# v1.net
KiCad netlist of a schematic drawn in EAGLE
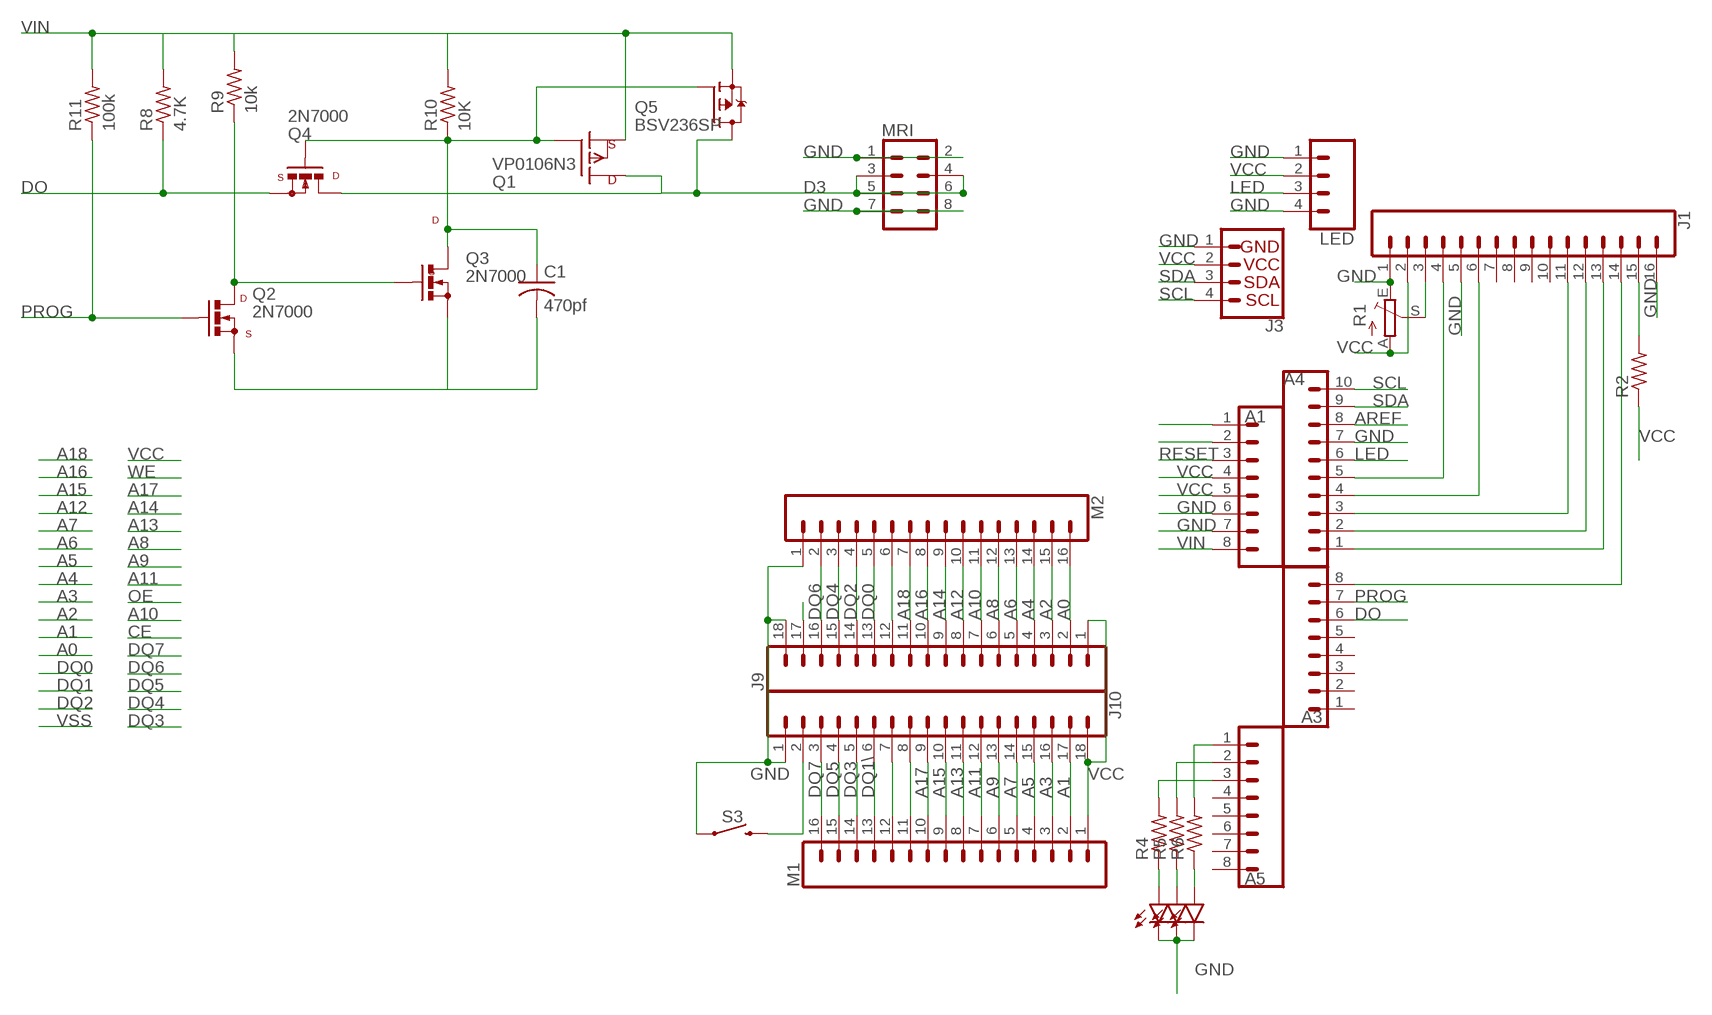
[diagram p0: schematic, sheet 1]

(export (version "E")
  (design (tool "Eeschema 10.0.6"))
  (components
    (comp (ref "A1")
      (value "CONN_08FEMALE_LOCK")
      (footprint "eagle-import:1X08_FEMALE_LOCK")
      (libsource (lib "eagle-import") (part "CONN_08FEMALE_LOCK"))
    )
    (comp (ref "A3")
      (value "CONN_08FEMALE_LOCK")
      (footprint "eagle-import:1X08_FEMALE_LOCK")
      (libsource (lib "eagle-import") (part "CONN_08FEMALE_LOCK"))
    )
    (comp (ref "A4")
      (value "CONN_10LOCK")
      (footprint "eagle-import:1X10_LOCK")
      (libsource (lib "eagle-import") (part "CONN_10LOCK"))
    )
    (comp (ref "A5")
      (value "CONN_08FEMALE_LOCK")
      (footprint "eagle-import:1X08_FEMALE_LOCK")
      (libsource (lib "eagle-import") (part "CONN_08FEMALE_LOCK"))
    )
    (comp (ref "C1")
      (value "470pf")
      (footprint "eagle-import:C025-025X050")
      (libsource (lib "eagle-import") (part "C-US025-025X050"))
    )
    (comp (ref "D1")
      (value "LED3MM")
      (footprint "eagle-import:LED_3MM")
      (libsource (lib "eagle-import") (part "LED3MM"))
    )
    (comp (ref "D2")
      (value "LED3MM")
      (footprint "eagle-import:LED_3MM")
      (libsource (lib "eagle-import") (part "LED3MM"))
    )
    (comp (ref "D3")
      (value "LED3MM")
      (footprint "eagle-import:LED_3MM")
      (libsource (lib "eagle-import") (part "LED3MM"))
    )
    (comp (ref "J1")
      (value "CONN_16LOCK")
      (footprint "eagle-import:1X16_LOCK")
      (libsource (lib "eagle-import") (part "CONN_16LOCK"))
    )
    (comp (ref "J3")
      (value "I2C_STANDARD")
      (footprint "eagle-import:1X04")
      (libsource (lib "eagle-import") (part "I2C_STANDARD"))
    )
    (comp (ref "J9")
      (value "CONN_18SILK")
      (footprint "eagle-import:1X18")
      (libsource (lib "eagle-import") (part "CONN_18SILK"))
    )
    (comp (ref "J10")
      (value "CONN_18SILK")
      (footprint "eagle-import:1X18")
      (libsource (lib "eagle-import") (part "CONN_18SILK"))
    )
    (comp (ref "LED")
      (value "CONN_04LOCK")
      (footprint "eagle-import:1X04_LOCK")
      (libsource (lib "eagle-import") (part "CONN_04LOCK"))
    )
    (comp (ref "M1")
      (value "CONN_16MACHIINE-PIN_LOCK")
      (footprint "eagle-import:1X16_MACHINE-PIN-HEADER_LOCK.004")
      (libsource (lib "eagle-import") (part "CONN_16MACHIINE-PIN_LOCK"))
    )
    (comp (ref "M2")
      (value "CONN_16MACHIINE-PIN_LOCK")
      (footprint "eagle-import:1X16_MACHINE-PIN-HEADER_LOCK.004")
      (libsource (lib "eagle-import") (part "CONN_16MACHIINE-PIN_LOCK"))
    )
    (comp (ref "MRI")
      (value "CONN_04X2")
      (footprint "eagle-import:2X4")
      (libsource (lib "eagle-import") (part "CONN_04X2"))
    )
    (comp (ref "Q1")
      (value "VP0106N3")
      (footprint "eagle-import:TO92-")
      (libsource (lib "eagle-import") (part "BSS110TO920"))
    )
    (comp (ref "Q2")
      (value "2N7000")
      (footprint "eagle-import:TO92-LINE")
      (libsource (lib "eagle-import") (part "BS170T092-"))
    )
    (comp (ref "Q3")
      (value "2N7000")
      (footprint "eagle-import:TO92-LINE")
      (libsource (lib "eagle-import") (part "BS170T092-"))
    )
    (comp (ref "Q4")
      (value "2N7000")
      (footprint "eagle-import:TO92-LINE")
      (libsource (lib "eagle-import") (part "BS170T092-"))
    )
    (comp (ref "Q5")
      (value "BSV236SP")
      (footprint "eagle-import:SOT363_INFINEON")
      (libsource (lib "eagle-import") (part "BSV236SP"))
    )
    (comp (ref "R1")
      (value "TRIM_EU-B64Y")
      (footprint "eagle-import:B64Y")
      (libsource (lib "eagle-import") (part "TRIM_EU-B64Y"))
    )
    (comp (ref "R2")
      (value "R-US_0309/10")
      (footprint "eagle-import:0309_10")
      (libsource (lib "eagle-import") (part "rcl_334_R-US_0309/10"))
    )
    (comp (ref "R4")
      (value "R-US_0309/10")
      (footprint "eagle-import:0309_10")
      (libsource (lib "eagle-import") (part "rcl_334_R-US_0309/10"))
    )
    (comp (ref "R5")
      (value "R-US_0309/10")
      (footprint "eagle-import:0309_10")
      (libsource (lib "eagle-import") (part "rcl_334_R-US_0309/10"))
    )
    (comp (ref "R6")
      (value "R-US_0309/10")
      (footprint "eagle-import:0309_10")
      (libsource (lib "eagle-import") (part "rcl_334_R-US_0309/10"))
    )
    (comp (ref "R8")
      (value "4.7K")
      (footprint "eagle-import:0207_2V")
      (libsource (lib "eagle-import") (part "R-US_0207/2V"))
    )
    (comp (ref "R9")
      (value "10k")
      (footprint "eagle-import:0309_10")
      (libsource (lib "eagle-import") (part "R-US_0309/10"))
    )
    (comp (ref "R10")
      (value "10K")
      (footprint "eagle-import:0207_2V")
      (libsource (lib "eagle-import") (part "R-US_0207/2V"))
    )
    (comp (ref "R11")
      (value "100k")
      (footprint "eagle-import:0309_10")
      (libsource (lib "eagle-import") (part "R-US_0309/10"))
    )
    (comp (ref "S3")
      (value "MOMENTARY-SWITCH-SPST-PTH-6.0MM")
      (footprint "eagle-import:TACTILE_SWITCH_PTH_6.0MM")
      (libsource (lib "eagle-import") (part "MOMENTARY-SWITCH-SPST-PTH-6.0MM"))
    )
  )
  (nets
    (net (code "1") (name "/A0") (class "Default")
      (node (ref "J9") (pin "2") (pinfunction "2_2") (pintype "passive"))
      (node (ref "M2") (pin "16") (pinfunction "16_16") (pintype "passive"))
    )
    (net (code "2") (name "/A1") (class "Default")
      (node (ref "J10") (pin "17") (pinfunction "17_17") (pintype "passive"))
      (node (ref "M1") (pin "2") (pinfunction "2_2") (pintype "passive"))
    )
    (net (code "3") (name "/A2") (class "Default")
      (node (ref "J9") (pin "3") (pinfunction "3_3") (pintype "passive"))
      (node (ref "M2") (pin "15") (pinfunction "15_15") (pintype "passive"))
    )
    (net (code "4") (name "/A3") (class "Default")
      (node (ref "J10") (pin "16") (pinfunction "16_16") (pintype "passive"))
      (node (ref "M1") (pin "3") (pinfunction "3_3") (pintype "passive"))
    )
    (net (code "5") (name "/A4") (class "Default")
      (node (ref "J9") (pin "4") (pinfunction "4_4") (pintype "passive"))
      (node (ref "M2") (pin "14") (pinfunction "14_14") (pintype "passive"))
    )
    (net (code "6") (name "/A5") (class "Default")
      (node (ref "J10") (pin "15") (pinfunction "15_15") (pintype "passive"))
      (node (ref "M1") (pin "4") (pinfunction "4_4") (pintype "passive"))
    )
    (net (code "7") (name "/A6") (class "Default")
      (node (ref "J9") (pin "5") (pinfunction "5_5") (pintype "passive"))
      (node (ref "M2") (pin "13") (pinfunction "13_13") (pintype "passive"))
    )
    (net (code "8") (name "/A7") (class "Default")
      (node (ref "J10") (pin "14") (pinfunction "14_14") (pintype "passive"))
      (node (ref "M1") (pin "5") (pinfunction "5_5") (pintype "passive"))
    )
    (net (code "9") (name "/A8") (class "Default")
      (node (ref "J9") (pin "6") (pinfunction "6_6") (pintype "passive"))
      (node (ref "M2") (pin "12") (pinfunction "12_12") (pintype "passive"))
    )
    (net (code "10") (name "/A9") (class "Default")
      (node (ref "J10") (pin "13") (pinfunction "13_13") (pintype "passive"))
      (node (ref "M1") (pin "6") (pinfunction "6_6") (pintype "passive"))
    )
    (net (code "11") (name "/A10") (class "Default")
      (node (ref "J9") (pin "7") (pinfunction "7_7") (pintype "passive"))
      (node (ref "M2") (pin "11") (pinfunction "11_11") (pintype "passive"))
    )
    (net (code "12") (name "/A11") (class "Default")
      (node (ref "J10") (pin "12") (pinfunction "12_12") (pintype "passive"))
      (node (ref "M1") (pin "7") (pinfunction "7_7") (pintype "passive"))
    )
    (net (code "13") (name "/A12") (class "Default")
      (node (ref "J9") (pin "8") (pinfunction "8_8") (pintype "passive"))
      (node (ref "M2") (pin "10") (pinfunction "10_10") (pintype "passive"))
    )
    (net (code "14") (name "/A13") (class "Default")
      (node (ref "J10") (pin "11") (pinfunction "11_11") (pintype "passive"))
      (node (ref "M1") (pin "8") (pinfunction "8_8") (pintype "passive"))
    )
    (net (code "15") (name "/A14") (class "Default")
      (node (ref "J9") (pin "9") (pinfunction "9_9") (pintype "passive"))
      (node (ref "M2") (pin "9") (pinfunction "9_9") (pintype "passive"))
    )
    (net (code "16") (name "/A15") (class "Default")
      (node (ref "J10") (pin "10") (pinfunction "10_10") (pintype "passive"))
      (node (ref "M1") (pin "9") (pinfunction "9_9") (pintype "passive"))
    )
    (net (code "17") (name "/A16") (class "Default")
      (node (ref "J9") (pin "10") (pinfunction "10_10") (pintype "passive"))
      (node (ref "M2") (pin "8") (pinfunction "8_8") (pintype "passive"))
    )
    (net (code "18") (name "/A17") (class "Default")
      (node (ref "J10") (pin "9") (pinfunction "9_9") (pintype "passive"))
      (node (ref "M1") (pin "10") (pinfunction "10_10") (pintype "passive"))
    )
    (net (code "19") (name "/A18") (class "Default")
      (node (ref "J9") (pin "11") (pinfunction "11_11") (pintype "passive"))
      (node (ref "M2") (pin "7") (pinfunction "7_7") (pintype "passive"))
    )
    (net (code "20") (name "/AREF") (class "Default")
      (node (ref "A4") (pin "8") (pinfunction "8_8") (pintype "passive"))
    )
    (net (code "22") (name "/D3") (class "Default")
      (node (ref "MRI") (pin "3") (pinfunction "3_3") (pintype "passive"))
      (node (ref "MRI") (pin "4") (pinfunction "4_4") (pintype "passive"))
      (node (ref "MRI") (pin "5") (pinfunction "5_5") (pintype "passive"))
      (node (ref "MRI") (pin "6") (pinfunction "6_6") (pintype "passive"))
      (node (ref "Q1") (pin "1") (pinfunction "D_1") (pintype "passive"))
      (node (ref "Q4") (pin "1") (pinfunction "D_1") (pintype "passive"))
      (node (ref "Q5") (pin "1") (pinfunction "D_1") (pintype "passive"))
      (node (ref "Q5") (pin "2") (pinfunction "D_2") (pintype "passive"))
      (node (ref "Q5") (pin "5") (pinfunction "D_5") (pintype "passive"))
      (node (ref "Q5") (pin "6") (pinfunction "D_6") (pintype "passive"))
    )
    (net (code "23") (name "/DO") (class "Default")
      (node (ref "A3") (pin "6") (pinfunction "6_6") (pintype "passive"))
      (node (ref "Q4") (pin "3") (pinfunction "S_3") (pintype "passive"))
      (node (ref "R8") (pin "1") (pinfunction "1_1") (pintype "passive"))
    )
    (net (code "24") (name "/DQ0") (class "Default")
      (node (ref "J9") (pin "13") (pinfunction "13_13") (pintype "passive"))
      (node (ref "M2") (pin "5") (pinfunction "5_5") (pintype "passive"))
    )
    (net (code "26") (name "/DQ1\\") (class "Default")
      (node (ref "J10") (pin "6") (pinfunction "6_6") (pintype "passive"))
      (node (ref "M1") (pin "13") (pinfunction "13_13") (pintype "passive"))
    )
    (net (code "27") (name "/DQ2") (class "Default")
      (node (ref "J9") (pin "14") (pinfunction "14_14") (pintype "passive"))
      (node (ref "M2") (pin "4") (pinfunction "4_4") (pintype "passive"))
    )
    (net (code "28") (name "/DQ3") (class "Default")
      (node (ref "J10") (pin "5") (pinfunction "5_5") (pintype "passive"))
      (node (ref "M1") (pin "14") (pinfunction "14_14") (pintype "passive"))
    )
    (net (code "29") (name "/DQ4") (class "Default")
      (node (ref "J9") (pin "15") (pinfunction "15_15") (pintype "passive"))
      (node (ref "M2") (pin "3") (pinfunction "3_3") (pintype "passive"))
    )
    (net (code "30") (name "/DQ5") (class "Default")
      (node (ref "J10") (pin "4") (pinfunction "4_4") (pintype "passive"))
      (node (ref "M1") (pin "15") (pinfunction "15_15") (pintype "passive"))
    )
    (net (code "31") (name "/DQ6") (class "Default")
      (node (ref "J9") (pin "16") (pinfunction "16_16") (pintype "passive"))
      (node (ref "M2") (pin "2") (pinfunction "2_2") (pintype "passive"))
    )
    (net (code "32") (name "/DQ7") (class "Default")
      (node (ref "J10") (pin "3") (pinfunction "3_3") (pintype "passive"))
      (node (ref "M1") (pin "16") (pinfunction "16_16") (pintype "passive"))
    )
    (net (code "33") (name "/GND") (class "Default")
      (node (ref "A1") (pin "6") (pinfunction "6_6") (pintype "passive"))
      (node (ref "A1") (pin "7") (pinfunction "7_7") (pintype "passive"))
      (node (ref "A4") (pin "7") (pinfunction "7_7") (pintype "passive"))
      (node (ref "D1") (pin "K") (pinfunction "C_K") (pintype "passive"))
      (node (ref "D2") (pin "K") (pinfunction "C_K") (pintype "passive"))
      (node (ref "D3") (pin "K") (pinfunction "C_K") (pintype "passive"))
      (node (ref "J1") (pin "1") (pinfunction "1_1") (pintype "passive"))
      (node (ref "J1") (pin "16") (pinfunction "16_16") (pintype "passive"))
      (node (ref "J1") (pin "5") (pinfunction "5_5") (pintype "passive"))
      (node (ref "J10") (pin "1") (pinfunction "1_1") (pintype "passive"))
      (node (ref "J3") (pin "1") (pinfunction "1_1") (pintype "power_in"))
      (node (ref "J9") (pin "18") (pinfunction "18_18") (pintype "passive"))
      (node (ref "LED") (pin "1") (pinfunction "1_1") (pintype "passive"))
      (node (ref "LED") (pin "4") (pinfunction "4_4") (pintype "passive"))
      (node (ref "M2") (pin "1") (pinfunction "1_1") (pintype "passive"))
      (node (ref "MRI") (pin "1") (pinfunction "1_1") (pintype "passive"))
      (node (ref "MRI") (pin "2") (pinfunction "2_2") (pintype "passive"))
      (node (ref "MRI") (pin "7") (pinfunction "7_7") (pintype "passive"))
      (node (ref "MRI") (pin "8") (pinfunction "8_8") (pintype "passive"))
      (node (ref "R1") (pin "E") (pinfunction "E_E") (pintype "passive"))
      (node (ref "S3") (pin "1") (pinfunction "1_1") (pintype "passive"))
    )
    (net (code "34") (name "/LED") (class "Default")
      (node (ref "A4") (pin "6") (pinfunction "6_6") (pintype "passive"))
      (node (ref "LED") (pin "3") (pinfunction "3_3") (pintype "passive"))
    )
    (net (code "36") (name "/PROG") (class "Default")
      (node (ref "A3") (pin "7") (pinfunction "7_7") (pintype "passive"))
      (node (ref "Q2") (pin "2") (pinfunction "G_2") (pintype "passive"))
      (node (ref "R11") (pin "1") (pinfunction "1_1") (pintype "passive"))
    )
    (net (code "37") (name "/RESET") (class "Default")
      (node (ref "A1") (pin "3") (pinfunction "3_3") (pintype "passive"))
    )
    (net (code "38") (name "/SCL") (class "Default")
      (node (ref "A4") (pin "10") (pinfunction "10_10") (pintype "passive"))
      (node (ref "J3") (pin "4") (pinfunction "4_4") (pintype "passive"))
    )
    (net (code "39") (name "/SDA") (class "Default")
      (node (ref "A4") (pin "9") (pinfunction "9_9") (pintype "passive"))
      (node (ref "J3") (pin "3") (pinfunction "3_3") (pintype "passive"))
    )
    (net (code "40") (name "/VCC") (class "Default")
      (node (ref "A1") (pin "4") (pinfunction "4_4") (pintype "passive"))
      (node (ref "A1") (pin "5") (pinfunction "5_5") (pintype "passive"))
      (node (ref "J1") (pin "2") (pinfunction "2_2") (pintype "passive"))
      (node (ref "J10") (pin "18") (pinfunction "18_18") (pintype "passive"))
      (node (ref "J3") (pin "2") (pinfunction "2_2") (pintype "power_in"))
      (node (ref "J9") (pin "1") (pinfunction "1_1") (pintype "passive"))
      (node (ref "LED") (pin "2") (pinfunction "2_2") (pintype "passive"))
      (node (ref "M1") (pin "1") (pinfunction "1_1") (pintype "passive"))
      (node (ref "R1") (pin "A") (pinfunction "A_A") (pintype "passive"))
      (node (ref "R2") (pin "1") (pinfunction "1_1") (pintype "passive"))
    )
    (net (code "41") (name "/VIN") (class "Default")
      (node (ref "A1") (pin "8") (pinfunction "8_8") (pintype "passive"))
      (node (ref "Q1") (pin "3") (pinfunction "S_3") (pintype "passive"))
      (node (ref "Q5") (pin "4") (pinfunction "S_4") (pintype "passive"))
      (node (ref "R10") (pin "2") (pinfunction "2_2") (pintype "passive"))
      (node (ref "R11") (pin "2") (pinfunction "2_2") (pintype "passive"))
      (node (ref "R8") (pin "2") (pinfunction "2_2") (pintype "passive"))
      (node (ref "R9") (pin "2") (pinfunction "2_2") (pintype "passive"))
    )
    (net (code "44") (name "Net-(A3-Pad8)") (class "Default")
      (node (ref "A3") (pin "8") (pinfunction "8_8") (pintype "passive"))
      (node (ref "J1") (pin "14") (pinfunction "14_14") (pintype "passive"))
    )
    (net (code "45") (name "Net-(A4-Pad1)") (class "Default")
      (node (ref "A4") (pin "1") (pinfunction "1_1") (pintype "passive"))
      (node (ref "J1") (pin "13") (pinfunction "13_13") (pintype "passive"))
    )
    (net (code "46") (name "Net-(A4-Pad2)") (class "Default")
      (node (ref "A4") (pin "2") (pinfunction "2_2") (pintype "passive"))
      (node (ref "J1") (pin "12") (pinfunction "12_12") (pintype "passive"))
    )
    (net (code "47") (name "Net-(A4-Pad3)") (class "Default")
      (node (ref "A4") (pin "3") (pinfunction "3_3") (pintype "passive"))
      (node (ref "J1") (pin "11") (pinfunction "11_11") (pintype "passive"))
    )
    (net (code "48") (name "Net-(A4-Pad4)") (class "Default")
      (node (ref "A4") (pin "4") (pinfunction "4_4") (pintype "passive"))
      (node (ref "J1") (pin "6") (pinfunction "6_6") (pintype "passive"))
    )
    (net (code "49") (name "Net-(A4-Pad5)") (class "Default")
      (node (ref "A4") (pin "5") (pinfunction "5_5") (pintype "passive"))
      (node (ref "J1") (pin "4") (pinfunction "4_4") (pintype "passive"))
    )
    (net (code "50") (name "Net-(A5-Pad1)") (class "Default")
      (node (ref "A5") (pin "1") (pinfunction "1_1") (pintype "passive"))
      (node (ref "R6") (pin "2") (pinfunction "2_2") (pintype "passive"))
    )
    (net (code "51") (name "Net-(A5-Pad2)") (class "Default")
      (node (ref "A5") (pin "2") (pinfunction "2_2") (pintype "passive"))
      (node (ref "R5") (pin "2") (pinfunction "2_2") (pintype "passive"))
    )
    (net (code "52") (name "Net-(A5-Pad3)") (class "Default")
      (node (ref "A5") (pin "3") (pinfunction "3_3") (pintype "passive"))
      (node (ref "R4") (pin "2") (pinfunction "2_2") (pintype "passive"))
    )
    (net (code "53") (name "Net-(D1-PadA)") (class "Default")
      (node (ref "D1") (pin "A") (pinfunction "A_A") (pintype "passive"))
      (node (ref "R4") (pin "1") (pinfunction "1_1") (pintype "passive"))
    )
    (net (code "54") (name "Net-(D2-PadA)") (class "Default")
      (node (ref "D2") (pin "A") (pinfunction "A_A") (pintype "passive"))
      (node (ref "R5") (pin "1") (pinfunction "1_1") (pintype "passive"))
    )
    (net (code "55") (name "Net-(D3-PadA)") (class "Default")
      (node (ref "D3") (pin "A") (pinfunction "A_A") (pintype "passive"))
      (node (ref "R6") (pin "1") (pinfunction "1_1") (pintype "passive"))
    )
    (net (code "56") (name "Net-(J1-Pad3)") (class "Default")
      (node (ref "J1") (pin "3") (pinfunction "3_3") (pintype "passive"))
      (node (ref "R1") (pin "S") (pinfunction "S_S") (pintype "passive"))
    )
    (net (code "57") (name "Net-(J1-Pad15)") (class "Default")
      (node (ref "J1") (pin "15") (pinfunction "15_15") (pintype "passive"))
      (node (ref "R2") (pin "2") (pinfunction "2_2") (pintype "passive"))
    )
    (net (code "58") (name "Net-(J9-Pad12)") (class "Default")
      (node (ref "J9") (pin "12") (pinfunction "12_12") (pintype "passive"))
      (node (ref "M2") (pin "6") (pinfunction "6_6") (pintype "passive"))
    )
    (net (code "59") (name "Net-(J10-Pad7)") (class "Default")
      (node (ref "J10") (pin "7") (pinfunction "7_7") (pintype "passive"))
      (node (ref "M1") (pin "12") (pinfunction "12_12") (pintype "passive"))
    )
    (net (code "60") (name "Net-(J10-Pad8)") (class "Default")
      (node (ref "J10") (pin "8") (pinfunction "8_8") (pintype "passive"))
      (node (ref "M1") (pin "11") (pinfunction "11_11") (pintype "passive"))
    )
    (net (code "61") (name "Net-(Q1-G)") (class "Default")
      (node (ref "C1") (pin "1") (pinfunction "1_1") (pintype "passive"))
      (node (ref "Q1") (pin "2") (pinfunction "G_2") (pintype "passive"))
      (node (ref "Q3") (pin "1") (pinfunction "D_1") (pintype "passive"))
      (node (ref "Q4") (pin "2") (pinfunction "G_2") (pintype "passive"))
      (node (ref "Q5") (pin "3") (pinfunction "G_3") (pintype "passive"))
      (node (ref "R10") (pin "1") (pinfunction "1_1") (pintype "passive"))
    )
    (net (code "62") (name "Net-(Q2-D)") (class "Default")
      (node (ref "Q2") (pin "1") (pinfunction "D_1") (pintype "passive"))
      (node (ref "Q3") (pin "2") (pinfunction "G_2") (pintype "passive"))
      (node (ref "R9") (pin "1") (pinfunction "1_1") (pintype "passive"))
    )
    (net (code "63") (name "Net-(Q2-S)") (class "Default")
      (node (ref "C1") (pin "2") (pinfunction "2_2") (pintype "passive"))
      (node (ref "Q2") (pin "3") (pinfunction "S_3") (pintype "passive"))
      (node (ref "Q3") (pin "3") (pinfunction "S_3") (pintype "passive"))
    )
    (net (code "64") (name "Net-(S3-2)") (class "Default")
      (node (ref "J10") (pin "2") (pinfunction "2_2") (pintype "passive"))
      (node (ref "S3") (pin "3") (pinfunction "2_3") (pintype "passive"))
    )
    (net (code "65") (name "unconnected-(A1-Pad1)") (class "Default")
      (node (ref "A1") (pin "1") (pinfunction "1_1") (pintype "passive"))
    )
    (net (code "66") (name "unconnected-(A1-Pad2)") (class "Default")
      (node (ref "A1") (pin "2") (pinfunction "2_2") (pintype "passive"))
    )
    (net (code "67") (name "unconnected-(A3-Pad1)") (class "Default")
      (node (ref "A3") (pin "1") (pinfunction "1_1") (pintype "passive"))
    )
    (net (code "68") (name "unconnected-(A3-Pad2)") (class "Default")
      (node (ref "A3") (pin "2") (pinfunction "2_2") (pintype "passive"))
    )
    (net (code "69") (name "unconnected-(A3-Pad3)") (class "Default")
      (node (ref "A3") (pin "3") (pinfunction "3_3") (pintype "passive"))
    )
    (net (code "70") (name "unconnected-(A3-Pad4)") (class "Default")
      (node (ref "A3") (pin "4") (pinfunction "4_4") (pintype "passive"))
    )
    (net (code "71") (name "unconnected-(A3-Pad5)") (class "Default")
      (node (ref "A3") (pin "5") (pinfunction "5_5") (pintype "passive"))
    )
    (net (code "72") (name "unconnected-(A5-Pad4)") (class "Default")
      (node (ref "A5") (pin "4") (pinfunction "4_4") (pintype "passive"))
    )
    (net (code "73") (name "unconnected-(A5-Pad5)") (class "Default")
      (node (ref "A5") (pin "5") (pinfunction "5_5") (pintype "passive"))
    )
    (net (code "74") (name "unconnected-(A5-Pad6)") (class "Default")
      (node (ref "A5") (pin "6") (pinfunction "6_6") (pintype "passive"))
    )
    (net (code "75") (name "unconnected-(A5-Pad7)") (class "Default")
      (node (ref "A5") (pin "7") (pinfunction "7_7") (pintype "passive"))
    )
    (net (code "76") (name "unconnected-(A5-Pad8)") (class "Default")
      (node (ref "A5") (pin "8") (pinfunction "8_8") (pintype "passive"))
    )
    (net (code "77") (name "unconnected-(J1-Pad7)") (class "Default")
      (node (ref "J1") (pin "7") (pinfunction "7_7") (pintype "passive"))
    )
    (net (code "78") (name "unconnected-(J1-Pad8)") (class "Default")
      (node (ref "J1") (pin "8") (pinfunction "8_8") (pintype "passive"))
    )
    (net (code "79") (name "unconnected-(J1-Pad9)") (class "Default")
      (node (ref "J1") (pin "9") (pinfunction "9_9") (pintype "passive"))
    )
    (net (code "80") (name "unconnected-(J1-Pad10)") (class "Default")
      (node (ref "J1") (pin "10") (pinfunction "10_10") (pintype "passive"))
    )
    (net (code "81") (name "unconnected-(J9-Pad17)") (class "Default")
      (node (ref "J9") (pin "17") (pinfunction "17_17") (pintype "passive"))
    )
  )
)
